# CO2_Sensor.net
KiCad netlist of a schematic drawn in Altium Designer
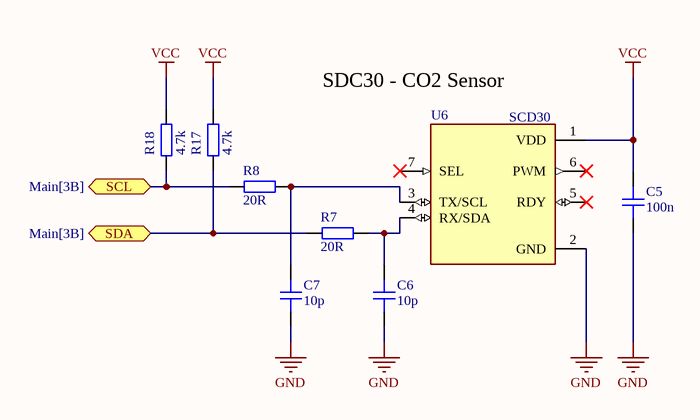
[diagram p0: CO2_Sensor.SchDoc]

(export (version "E")
  (design (tool "Eeschema 10.0.6"))
  (components
    (comp (ref "C5")
      (value "100n")
      (footprint "CAP_0805")
      (description "Capacitor SMD 0805")
      (libsource (lib "Schematic-Lib-PhilsLab") (part "CAP_0805"))
    )
    (comp (ref "C6")
      (value "10p")
      (footprint "CAP_0805")
      (description "Capacitor SMD 0805")
      (libsource (lib "Schematic-Lib-PhilsLab") (part "CAP_0805"))
    )
    (comp (ref "C7")
      (value "10p")
      (footprint "CAP_0805")
      (description "Capacitor SMD 0805")
      (libsource (lib "Schematic-Lib-PhilsLab") (part "CAP_0805"))
    )
    (comp (ref "R7")
      (value "20R")
      (footprint "RES_0805")
      (description "Resistor SMD 0805")
      (libsource (lib "Schematic-Lib-PhilsLab") (part "RES_0805"))
    )
    (comp (ref "R8")
      (value "20R")
      (footprint "RES_0805")
      (description "Resistor SMD 0805")
      (libsource (lib "Schematic-Lib-PhilsLab") (part "RES_0805"))
    )
    (comp (ref "R17")
      (value "4.7k")
      (footprint "Footprint-Lib-PhilsLab:RES_0805")
      (description "Resistor SMD 0805")
      (libsource (lib "Schematic-Lib-PhilsLab") (part "RES_0805"))
    )
    (comp (ref "R18")
      (value "4.7k")
      (footprint "Footprint-Lib-PhilsLab:RES_0805")
      (description "Resistor SMD 0805")
      (libsource (lib "Schematic-Lib-PhilsLab") (part "RES_0805"))
    )
    (comp (ref "U6")
      (value "SCD30")
      (footprint "SDC30")
      (description "SCD30 Series 5.5 V 75 mA Â±3% Carbon Dioxide (CO2) Sensor Module")
      (libsource (lib "SCD30") (part "SCD30"))
    )
  )
  (nets
    (net (code "1") (name "/SCL") (class "Default")
      (node (ref "R18") (pin "2") (pinfunction "2_2") (pintype "passive"))
      (node (ref "R8") (pin "2") (pinfunction "2_2") (pintype "passive"))
    )
    (net (code "2") (name "/SDA") (class "Default")
      (node (ref "R17") (pin "2") (pinfunction "2_2") (pintype "passive"))
      (node (ref "R7") (pin "2") (pinfunction "2_2") (pintype "passive"))
    )
    (net (code "3") (name "GND") (class "Default")
      (node (ref "C5") (pin "1") (pinfunction "1_1") (pintype "passive"))
      (node (ref "C6") (pin "1") (pinfunction "1_1") (pintype "passive"))
      (node (ref "C7") (pin "1") (pinfunction "1_1") (pintype "passive"))
      (node (ref "U6") (pin "2") (pinfunction "GND_2") (pintype "power_in"))
    )
    (net (code "4") (name "Net-(U6-RX{slash}SDA)") (class "Default")
      (node (ref "C6") (pin "2") (pinfunction "2_2") (pintype "passive"))
      (node (ref "R7") (pin "1") (pinfunction "1_1") (pintype "passive"))
      (node (ref "U6") (pin "4") (pinfunction "RX/SDA_4") (pintype "bidirectional"))
    )
    (net (code "5") (name "Net-(U6-TX{slash}SCL)") (class "Default")
      (node (ref "C7") (pin "2") (pinfunction "2_2") (pintype "passive"))
      (node (ref "R8") (pin "1") (pinfunction "1_1") (pintype "passive"))
      (node (ref "U6") (pin "3") (pinfunction "TX/SCL_3") (pintype "bidirectional"))
    )
    (net (code "6") (name "VCC") (class "Default")
      (node (ref "C5") (pin "2") (pinfunction "2_2") (pintype "passive"))
      (node (ref "R17") (pin "1") (pinfunction "1_1") (pintype "passive"))
      (node (ref "R18") (pin "1") (pinfunction "1_1") (pintype "passive"))
      (node (ref "U6") (pin "1") (pinfunction "VDD_1") (pintype "power_in"))
    )
    (net (code "7") (name "unconnected-(U6-PWM-Pad6)") (class "Default")
      (node (ref "U6") (pin "6") (pinfunction "PWM_6") (pintype "output+no_connect"))
    )
    (net (code "8") (name "unconnected-(U6-RDY-Pad5)") (class "Default")
      (node (ref "U6") (pin "5") (pinfunction "RDY_5") (pintype "bidirectional+no_connect"))
    )
    (net (code "9") (name "unconnected-(U6-SEL-Pad7)") (class "Default")
      (node (ref "U6") (pin "7") (pinfunction "SEL_7") (pintype "input+no_connect"))
    )
  )
)
